# KY-012-Active-buzzer-module_2025-10-18.net
KiCad netlist of a schematic drawn in Altium Designer
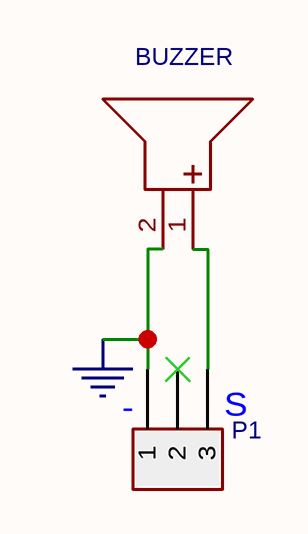
[diagram p0: KY-012-Active-buzzer-module_2025-10-18.schdoc]

(export (version "E")
  (design (tool "Eeschema 10.0.6"))
  (components
    (comp (ref "BUZZER")
      (value "ZL-DCY09605-2705P-5")
      (fields (field (name "MANUFACTURER") "ZLFY") (field (name "CONTRIBUTOR") "LCSC"))
      (libsource (lib "altium-import") (part "root_3_ZL-DCY09605-2705P-5_"))
    )
    (comp (ref "P1")
      (value "Header-Male-2.54_1x3")
      (fields (field (name "MANUFACTURER") "LCSC"))
      (libsource (lib "altium-import") (part "root_3_Header-Male-2.54_1x3_"))
    )
  )
  (nets
    (net (code "1") (name "GND") (class "Default")
      (node (ref "BUZZER") (pin "2") (pinfunction "-_2") (pintype "passive"))
      (node (ref "P1") (pin "1") (pinfunction "1_1") (pintype "passive"))
    )
    (net (code "2") (name "Net-(BUZZER-+)") (class "Default")
      (node (ref "BUZZER") (pin "1") (pinfunction "+_1") (pintype "passive"))
      (node (ref "P1") (pin "3") (pinfunction "3_3") (pintype "passive"))
    )
    (net (code "3") (name "unconnected-(P1-Pad2)") (class "Default")
      (node (ref "P1") (pin "2") (pinfunction "2_2") (pintype "passive+no_connect"))
    )
  )
)
